# Control_board.net
KiCad netlist of a schematic drawn in EAGLE
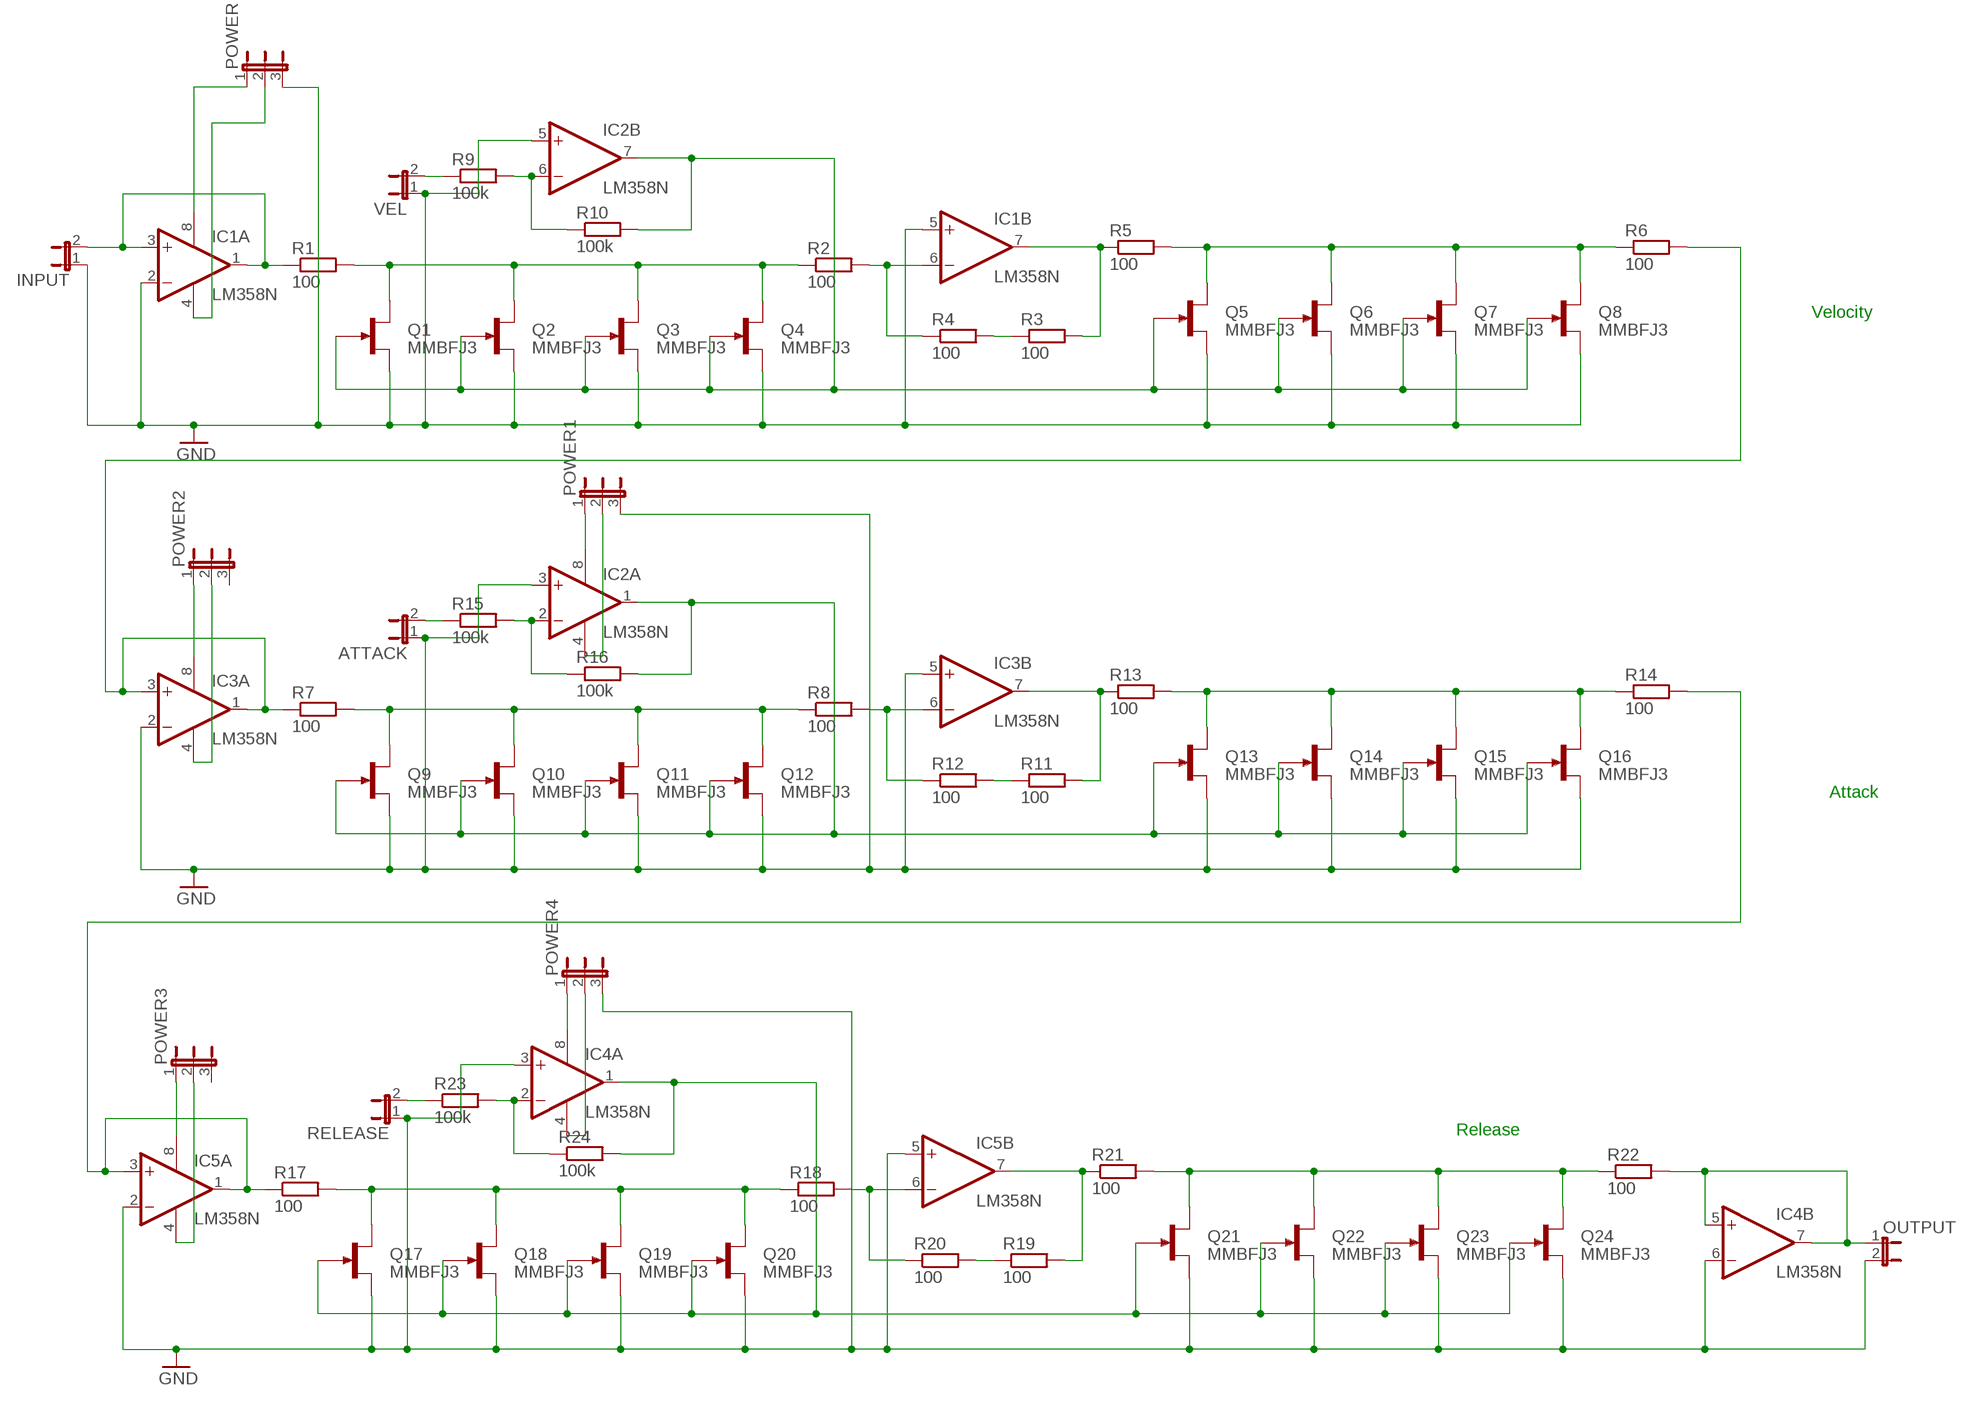
[diagram p0: schematic, sheet 1]

(export (version "E")
  (design (tool "Eeschema 10.0.6"))
  (components
    (comp (ref "ATTACK")
      (value "JP1E")
      (footprint "eagle-import:JP1")
      (libsource (lib "eagle-import") (part "JP1E"))
    )
    (comp (ref "IC1")
      (value "LM358N")
      (footprint "eagle-import:DIL08")
      (libsource (lib "eagle-import") (part "LM358N"))
    )
    (comp (ref "IC2")
      (value "LM358N")
      (footprint "eagle-import:DIL08")
      (libsource (lib "eagle-import") (part "LM358N"))
    )
    (comp (ref "IC3")
      (value "LM358N")
      (footprint "eagle-import:DIL08")
      (libsource (lib "eagle-import") (part "LM358N"))
    )
    (comp (ref "IC4")
      (value "LM358N")
      (footprint "eagle-import:DIL08")
      (libsource (lib "eagle-import") (part "LM358N"))
    )
    (comp (ref "IC5")
      (value "LM358N")
      (footprint "eagle-import:DIL08")
      (libsource (lib "eagle-import") (part "LM358N"))
    )
    (comp (ref "INPUT")
      (value "JP1E")
      (footprint "eagle-import:JP1")
      (libsource (lib "eagle-import") (part "JP1E"))
    )
    (comp (ref "OUTPUT")
      (value "JP1E")
      (footprint "eagle-import:JP1")
      (libsource (lib "eagle-import") (part "JP1E"))
    )
    (comp (ref "POWER")
      (value "JP2E")
      (footprint "eagle-import:JP2")
      (libsource (lib "eagle-import") (part "JP2E"))
    )
    (comp (ref "POWER1")
      (value "JP2E")
      (footprint "eagle-import:JP2")
      (libsource (lib "eagle-import") (part "JP2E"))
    )
    (comp (ref "POWER2")
      (value "JP2E")
      (footprint "eagle-import:JP2")
      (libsource (lib "eagle-import") (part "JP2E"))
    )
    (comp (ref "POWER3")
      (value "JP2E")
      (footprint "eagle-import:JP2")
      (libsource (lib "eagle-import") (part "JP2E"))
    )
    (comp (ref "POWER4")
      (value "JP2E")
      (footprint "eagle-import:JP2")
      (libsource (lib "eagle-import") (part "JP2E"))
    )
    (comp (ref "Q1")
      (value "MMBFJ3")
      (footprint "eagle-import:SOT23")
      (libsource (lib "eagle-import") (part "MMBFJ3"))
    )
    (comp (ref "Q2")
      (value "MMBFJ3")
      (footprint "eagle-import:SOT23")
      (libsource (lib "eagle-import") (part "MMBFJ3"))
    )
    (comp (ref "Q3")
      (value "MMBFJ3")
      (footprint "eagle-import:SOT23")
      (libsource (lib "eagle-import") (part "MMBFJ3"))
    )
    (comp (ref "Q4")
      (value "MMBFJ3")
      (footprint "eagle-import:SOT23")
      (libsource (lib "eagle-import") (part "MMBFJ3"))
    )
    (comp (ref "Q5")
      (value "MMBFJ3")
      (footprint "eagle-import:SOT23")
      (libsource (lib "eagle-import") (part "MMBFJ3"))
    )
    (comp (ref "Q6")
      (value "MMBFJ3")
      (footprint "eagle-import:SOT23")
      (libsource (lib "eagle-import") (part "MMBFJ3"))
    )
    (comp (ref "Q7")
      (value "MMBFJ3")
      (footprint "eagle-import:SOT23")
      (libsource (lib "eagle-import") (part "MMBFJ3"))
    )
    (comp (ref "Q8")
      (value "MMBFJ3")
      (footprint "eagle-import:SOT23")
      (libsource (lib "eagle-import") (part "MMBFJ3"))
    )
    (comp (ref "Q9")
      (value "MMBFJ3")
      (footprint "eagle-import:SOT23")
      (libsource (lib "eagle-import") (part "MMBFJ3"))
    )
    (comp (ref "Q10")
      (value "MMBFJ3")
      (footprint "eagle-import:SOT23")
      (libsource (lib "eagle-import") (part "MMBFJ3"))
    )
    (comp (ref "Q11")
      (value "MMBFJ3")
      (footprint "eagle-import:SOT23")
      (libsource (lib "eagle-import") (part "MMBFJ3"))
    )
    (comp (ref "Q12")
      (value "MMBFJ3")
      (footprint "eagle-import:SOT23")
      (libsource (lib "eagle-import") (part "MMBFJ3"))
    )
    (comp (ref "Q13")
      (value "MMBFJ3")
      (footprint "eagle-import:SOT23")
      (libsource (lib "eagle-import") (part "MMBFJ3"))
    )
    (comp (ref "Q14")
      (value "MMBFJ3")
      (footprint "eagle-import:SOT23")
      (libsource (lib "eagle-import") (part "MMBFJ3"))
    )
    (comp (ref "Q15")
      (value "MMBFJ3")
      (footprint "eagle-import:SOT23")
      (libsource (lib "eagle-import") (part "MMBFJ3"))
    )
    (comp (ref "Q16")
      (value "MMBFJ3")
      (footprint "eagle-import:SOT23")
      (libsource (lib "eagle-import") (part "MMBFJ3"))
    )
    (comp (ref "Q17")
      (value "MMBFJ3")
      (footprint "eagle-import:SOT23")
      (libsource (lib "eagle-import") (part "MMBFJ3"))
    )
    (comp (ref "Q18")
      (value "MMBFJ3")
      (footprint "eagle-import:SOT23")
      (libsource (lib "eagle-import") (part "MMBFJ3"))
    )
    (comp (ref "Q19")
      (value "MMBFJ3")
      (footprint "eagle-import:SOT23")
      (libsource (lib "eagle-import") (part "MMBFJ3"))
    )
    (comp (ref "Q20")
      (value "MMBFJ3")
      (footprint "eagle-import:SOT23")
      (libsource (lib "eagle-import") (part "MMBFJ3"))
    )
    (comp (ref "Q21")
      (value "MMBFJ3")
      (footprint "eagle-import:SOT23")
      (libsource (lib "eagle-import") (part "MMBFJ3"))
    )
    (comp (ref "Q22")
      (value "MMBFJ3")
      (footprint "eagle-import:SOT23")
      (libsource (lib "eagle-import") (part "MMBFJ3"))
    )
    (comp (ref "Q23")
      (value "MMBFJ3")
      (footprint "eagle-import:SOT23")
      (libsource (lib "eagle-import") (part "MMBFJ3"))
    )
    (comp (ref "Q24")
      (value "MMBFJ3")
      (footprint "eagle-import:SOT23")
      (libsource (lib "eagle-import") (part "MMBFJ3"))
    )
    (comp (ref "R1")
      (value "100")
      (footprint "eagle-import:0204_7")
      (libsource (lib "eagle-import") (part "R-EU_0204/7"))
    )
    (comp (ref "R2")
      (value "100")
      (footprint "eagle-import:0204_7")
      (libsource (lib "eagle-import") (part "R-EU_0204/7"))
    )
    (comp (ref "R3")
      (value "100")
      (footprint "eagle-import:0204_7")
      (libsource (lib "eagle-import") (part "R-EU_0204/7"))
    )
    (comp (ref "R4")
      (value "100")
      (footprint "eagle-import:0204_7")
      (libsource (lib "eagle-import") (part "R-EU_0204/7"))
    )
    (comp (ref "R5")
      (value "100")
      (footprint "eagle-import:0204_7")
      (libsource (lib "eagle-import") (part "R-EU_0204/7"))
    )
    (comp (ref "R6")
      (value "100")
      (footprint "eagle-import:0204_7")
      (libsource (lib "eagle-import") (part "R-EU_0204/7"))
    )
    (comp (ref "R7")
      (value "100")
      (footprint "eagle-import:0204_7")
      (libsource (lib "eagle-import") (part "R-EU_0204/7"))
    )
    (comp (ref "R8")
      (value "100")
      (footprint "eagle-import:0204_7")
      (libsource (lib "eagle-import") (part "R-EU_0204/7"))
    )
    (comp (ref "R9")
      (value "100k")
      (footprint "eagle-import:0204_7")
      (libsource (lib "eagle-import") (part "R-EU_0204/7"))
    )
    (comp (ref "R10")
      (value "100k")
      (footprint "eagle-import:0204_7")
      (libsource (lib "eagle-import") (part "R-EU_0204/7"))
    )
    (comp (ref "R11")
      (value "100")
      (footprint "eagle-import:0204_7")
      (libsource (lib "eagle-import") (part "R-EU_0204/7"))
    )
    (comp (ref "R12")
      (value "100")
      (footprint "eagle-import:0204_7")
      (libsource (lib "eagle-import") (part "R-EU_0204/7"))
    )
    (comp (ref "R13")
      (value "100")
      (footprint "eagle-import:0204_7")
      (libsource (lib "eagle-import") (part "R-EU_0204/7"))
    )
    (comp (ref "R14")
      (value "100")
      (footprint "eagle-import:0204_7")
      (libsource (lib "eagle-import") (part "R-EU_0204/7"))
    )
    (comp (ref "R15")
      (value "100k")
      (footprint "eagle-import:0204_7")
      (libsource (lib "eagle-import") (part "R-EU_0204/7"))
    )
    (comp (ref "R16")
      (value "100k")
      (footprint "eagle-import:0204_7")
      (libsource (lib "eagle-import") (part "R-EU_0204/7"))
    )
    (comp (ref "R17")
      (value "100")
      (footprint "eagle-import:0204_7")
      (libsource (lib "eagle-import") (part "R-EU_0204/7"))
    )
    (comp (ref "R18")
      (value "100")
      (footprint "eagle-import:0204_7")
      (libsource (lib "eagle-import") (part "R-EU_0204/7"))
    )
    (comp (ref "R19")
      (value "100")
      (footprint "eagle-import:0204_7")
      (libsource (lib "eagle-import") (part "R-EU_0204/7"))
    )
    (comp (ref "R20")
      (value "100")
      (footprint "eagle-import:0204_7")
      (libsource (lib "eagle-import") (part "R-EU_0204/7"))
    )
    (comp (ref "R21")
      (value "100")
      (footprint "eagle-import:0204_7")
      (libsource (lib "eagle-import") (part "R-EU_0204/7"))
    )
    (comp (ref "R22")
      (value "100")
      (footprint "eagle-import:0204_7")
      (libsource (lib "eagle-import") (part "R-EU_0204/7"))
    )
    (comp (ref "R23")
      (value "100k")
      (footprint "eagle-import:0204_7")
      (libsource (lib "eagle-import") (part "R-EU_0204/7"))
    )
    (comp (ref "R24")
      (value "100k")
      (footprint "eagle-import:0204_7")
      (libsource (lib "eagle-import") (part "R-EU_0204/7"))
    )
    (comp (ref "RELEASE")
      (value "JP1E")
      (footprint "eagle-import:JP1")
      (libsource (lib "eagle-import") (part "JP1E"))
    )
    (comp (ref "VEL")
      (value "JP1E")
      (footprint "eagle-import:JP1")
      (libsource (lib "eagle-import") (part "JP1E"))
    )
  )
  (nets
    (net (code "1") (name "GND") (class "Default")
      (node (ref "ATTACK") (pin "1") (pinfunction "1_1") (pintype "passive"))
      (node (ref "IC1") (pin "2") (pinfunction "-IN_2") (pintype "input"))
      (node (ref "IC1") (pin "5") (pinfunction "+IN_5") (pintype "input"))
      (node (ref "IC2") (pin "3") (pinfunction "+IN_3") (pintype "input"))
      (node (ref "IC2") (pin "5") (pinfunction "+IN_5") (pintype "input"))
      (node (ref "IC3") (pin "2") (pinfunction "-IN_2") (pintype "input"))
      (node (ref "IC3") (pin "5") (pinfunction "+IN_5") (pintype "input"))
      (node (ref "IC4") (pin "3") (pinfunction "+IN_3") (pintype "input"))
      (node (ref "IC4") (pin "6") (pinfunction "-IN_6") (pintype "input"))
      (node (ref "IC5") (pin "2") (pinfunction "-IN_2") (pintype "input"))
      (node (ref "IC5") (pin "5") (pinfunction "+IN_5") (pintype "input"))
      (node (ref "INPUT") (pin "1") (pinfunction "1_1") (pintype "passive"))
      (node (ref "OUTPUT") (pin "2") (pinfunction "2_2") (pintype "passive"))
      (node (ref "POWER") (pin "3") (pinfunction "3_3") (pintype "passive"))
      (node (ref "POWER1") (pin "3") (pinfunction "3_3") (pintype "passive"))
      (node (ref "POWER4") (pin "3") (pinfunction "3_3") (pintype "passive"))
      (node (ref "Q1") (pin "2") (pinfunction "S_2") (pintype "passive"))
      (node (ref "Q10") (pin "2") (pinfunction "S_2") (pintype "passive"))
      (node (ref "Q11") (pin "2") (pinfunction "S_2") (pintype "passive"))
      (node (ref "Q12") (pin "2") (pinfunction "S_2") (pintype "passive"))
      (node (ref "Q13") (pin "2") (pinfunction "S_2") (pintype "passive"))
      (node (ref "Q14") (pin "2") (pinfunction "S_2") (pintype "passive"))
      (node (ref "Q15") (pin "2") (pinfunction "S_2") (pintype "passive"))
      (node (ref "Q16") (pin "2") (pinfunction "S_2") (pintype "passive"))
      (node (ref "Q17") (pin "2") (pinfunction "S_2") (pintype "passive"))
      (node (ref "Q18") (pin "2") (pinfunction "S_2") (pintype "passive"))
      (node (ref "Q19") (pin "2") (pinfunction "S_2") (pintype "passive"))
      (node (ref "Q2") (pin "2") (pinfunction "S_2") (pintype "passive"))
      (node (ref "Q20") (pin "2") (pinfunction "S_2") (pintype "passive"))
      (node (ref "Q21") (pin "2") (pinfunction "S_2") (pintype "passive"))
      (node (ref "Q22") (pin "2") (pinfunction "S_2") (pintype "passive"))
      (node (ref "Q23") (pin "2") (pinfunction "S_2") (pintype "passive"))
      (node (ref "Q24") (pin "2") (pinfunction "S_2") (pintype "passive"))
      (node (ref "Q3") (pin "2") (pinfunction "S_2") (pintype "passive"))
      (node (ref "Q4") (pin "2") (pinfunction "S_2") (pintype "passive"))
      (node (ref "Q5") (pin "2") (pinfunction "S_2") (pintype "passive"))
      (node (ref "Q6") (pin "2") (pinfunction "S_2") (pintype "passive"))
      (node (ref "Q7") (pin "2") (pinfunction "S_2") (pintype "passive"))
      (node (ref "Q8") (pin "2") (pinfunction "S_2") (pintype "passive"))
      (node (ref "Q9") (pin "2") (pinfunction "S_2") (pintype "passive"))
      (node (ref "RELEASE") (pin "1") (pinfunction "1_1") (pintype "passive"))
      (node (ref "VEL") (pin "1") (pinfunction "1_1") (pintype "passive"))
    )
    (net (code "2") (name "Net-(ATTACK-Pad2)") (class "Default")
      (node (ref "ATTACK") (pin "2") (pinfunction "2_2") (pintype "passive"))
      (node (ref "R15") (pin "1") (pinfunction "1_1") (pintype "passive"))
    )
    (net (code "3") (name "Net-(IC1A-+IN)") (class "Default")
      (node (ref "IC1") (pin "1") (pinfunction "OUT_1") (pintype "output"))
      (node (ref "IC1") (pin "3") (pinfunction "+IN_3") (pintype "input"))
      (node (ref "INPUT") (pin "2") (pinfunction "2_2") (pintype "passive"))
      (node (ref "R1") (pin "1") (pinfunction "1_1") (pintype "passive"))
    )
    (net (code "4") (name "Net-(IC1B--IN)") (class "Default")
      (node (ref "IC1") (pin "6") (pinfunction "-IN_6") (pintype "input"))
      (node (ref "R2") (pin "2") (pinfunction "2_2") (pintype "passive"))
      (node (ref "R4") (pin "1") (pinfunction "1_1") (pintype "passive"))
    )
    (net (code "5") (name "Net-(IC1B-OUT)") (class "Default")
      (node (ref "IC1") (pin "7") (pinfunction "OUT_7") (pintype "output"))
      (node (ref "R3") (pin "2") (pinfunction "2_2") (pintype "passive"))
      (node (ref "R5") (pin "1") (pinfunction "1_1") (pintype "passive"))
    )
    (net (code "6") (name "Net-(IC1C-V+)") (class "Default")
      (node (ref "IC1") (pin "8") (pinfunction "V+_8") (pintype "power_in"))
      (node (ref "POWER") (pin "1") (pinfunction "1_1") (pintype "passive"))
    )
    (net (code "7") (name "Net-(IC1C-V-)") (class "Default")
      (node (ref "IC1") (pin "4") (pinfunction "V-_4") (pintype "power_in"))
      (node (ref "POWER") (pin "2") (pinfunction "2_2") (pintype "passive"))
    )
    (net (code "8") (name "Net-(IC2A--IN)") (class "Default")
      (node (ref "IC2") (pin "2") (pinfunction "-IN_2") (pintype "input"))
      (node (ref "R15") (pin "2") (pinfunction "2_2") (pintype "passive"))
      (node (ref "R16") (pin "1") (pinfunction "1_1") (pintype "passive"))
    )
    (net (code "9") (name "Net-(IC2A-OUT)") (class "Default")
      (node (ref "IC2") (pin "1") (pinfunction "OUT_1") (pintype "output"))
      (node (ref "Q10") (pin "3") (pinfunction "G_3") (pintype "passive"))
      (node (ref "Q11") (pin "3") (pinfunction "G_3") (pintype "passive"))
      (node (ref "Q12") (pin "3") (pinfunction "G_3") (pintype "passive"))
      (node (ref "Q13") (pin "3") (pinfunction "G_3") (pintype "passive"))
      (node (ref "Q14") (pin "3") (pinfunction "G_3") (pintype "passive"))
      (node (ref "Q15") (pin "3") (pinfunction "G_3") (pintype "passive"))
      (node (ref "Q16") (pin "3") (pinfunction "G_3") (pintype "passive"))
      (node (ref "Q9") (pin "3") (pinfunction "G_3") (pintype "passive"))
      (node (ref "R16") (pin "2") (pinfunction "2_2") (pintype "passive"))
    )
    (net (code "10") (name "Net-(IC2B--IN)") (class "Default")
      (node (ref "IC2") (pin "6") (pinfunction "-IN_6") (pintype "input"))
      (node (ref "R10") (pin "1") (pinfunction "1_1") (pintype "passive"))
      (node (ref "R9") (pin "2") (pinfunction "2_2") (pintype "passive"))
    )
    (net (code "11") (name "Net-(IC2B-OUT)") (class "Default")
      (node (ref "IC2") (pin "7") (pinfunction "OUT_7") (pintype "output"))
      (node (ref "Q1") (pin "3") (pinfunction "G_3") (pintype "passive"))
      (node (ref "Q2") (pin "3") (pinfunction "G_3") (pintype "passive"))
      (node (ref "Q3") (pin "3") (pinfunction "G_3") (pintype "passive"))
      (node (ref "Q4") (pin "3") (pinfunction "G_3") (pintype "passive"))
      (node (ref "Q5") (pin "3") (pinfunction "G_3") (pintype "passive"))
      (node (ref "Q6") (pin "3") (pinfunction "G_3") (pintype "passive"))
      (node (ref "Q7") (pin "3") (pinfunction "G_3") (pintype "passive"))
      (node (ref "Q8") (pin "3") (pinfunction "G_3") (pintype "passive"))
      (node (ref "R10") (pin "2") (pinfunction "2_2") (pintype "passive"))
    )
    (net (code "12") (name "Net-(IC2C-V+)") (class "Default")
      (node (ref "IC2") (pin "8") (pinfunction "V+_8") (pintype "power_in"))
      (node (ref "POWER1") (pin "1") (pinfunction "1_1") (pintype "passive"))
    )
    (net (code "13") (name "Net-(IC2C-V-)") (class "Default")
      (node (ref "IC2") (pin "4") (pinfunction "V-_4") (pintype "power_in"))
      (node (ref "POWER1") (pin "2") (pinfunction "2_2") (pintype "passive"))
    )
    (net (code "14") (name "Net-(IC3A-+IN)") (class "Default")
      (node (ref "IC3") (pin "1") (pinfunction "OUT_1") (pintype "output"))
      (node (ref "IC3") (pin "3") (pinfunction "+IN_3") (pintype "input"))
      (node (ref "R6") (pin "2") (pinfunction "2_2") (pintype "passive"))
      (node (ref "R7") (pin "1") (pinfunction "1_1") (pintype "passive"))
    )
    (net (code "15") (name "Net-(IC3B--IN)") (class "Default")
      (node (ref "IC3") (pin "6") (pinfunction "-IN_6") (pintype "input"))
      (node (ref "R12") (pin "1") (pinfunction "1_1") (pintype "passive"))
      (node (ref "R8") (pin "2") (pinfunction "2_2") (pintype "passive"))
    )
    (net (code "16") (name "Net-(IC3B-OUT)") (class "Default")
      (node (ref "IC3") (pin "7") (pinfunction "OUT_7") (pintype "output"))
      (node (ref "R11") (pin "2") (pinfunction "2_2") (pintype "passive"))
      (node (ref "R13") (pin "1") (pinfunction "1_1") (pintype "passive"))
    )
    (net (code "17") (name "Net-(IC3C-V+)") (class "Default")
      (node (ref "IC3") (pin "8") (pinfunction "V+_8") (pintype "power_in"))
      (node (ref "POWER2") (pin "1") (pinfunction "1_1") (pintype "passive"))
    )
    (net (code "18") (name "Net-(IC3C-V-)") (class "Default")
      (node (ref "IC3") (pin "4") (pinfunction "V-_4") (pintype "power_in"))
      (node (ref "POWER2") (pin "2") (pinfunction "2_2") (pintype "passive"))
    )
    (net (code "19") (name "Net-(IC4A--IN)") (class "Default")
      (node (ref "IC4") (pin "2") (pinfunction "-IN_2") (pintype "input"))
      (node (ref "R23") (pin "2") (pinfunction "2_2") (pintype "passive"))
      (node (ref "R24") (pin "1") (pinfunction "1_1") (pintype "passive"))
    )
    (net (code "20") (name "Net-(IC4A-OUT)") (class "Default")
      (node (ref "IC4") (pin "1") (pinfunction "OUT_1") (pintype "output"))
      (node (ref "Q17") (pin "3") (pinfunction "G_3") (pintype "passive"))
      (node (ref "Q18") (pin "3") (pinfunction "G_3") (pintype "passive"))
      (node (ref "Q19") (pin "3") (pinfunction "G_3") (pintype "passive"))
      (node (ref "Q20") (pin "3") (pinfunction "G_3") (pintype "passive"))
      (node (ref "Q21") (pin "3") (pinfunction "G_3") (pintype "passive"))
      (node (ref "Q22") (pin "3") (pinfunction "G_3") (pintype "passive"))
      (node (ref "Q23") (pin "3") (pinfunction "G_3") (pintype "passive"))
      (node (ref "Q24") (pin "3") (pinfunction "G_3") (pintype "passive"))
      (node (ref "R24") (pin "2") (pinfunction "2_2") (pintype "passive"))
    )
    (net (code "21") (name "Net-(IC4B-+IN)") (class "Default")
      (node (ref "IC4") (pin "5") (pinfunction "+IN_5") (pintype "input"))
      (node (ref "IC4") (pin "7") (pinfunction "OUT_7") (pintype "output"))
      (node (ref "OUTPUT") (pin "1") (pinfunction "1_1") (pintype "passive"))
      (node (ref "R22") (pin "2") (pinfunction "2_2") (pintype "passive"))
    )
    (net (code "22") (name "Net-(IC4C-V+)") (class "Default")
      (node (ref "IC4") (pin "8") (pinfunction "V+_8") (pintype "power_in"))
      (node (ref "POWER4") (pin "1") (pinfunction "1_1") (pintype "passive"))
    )
    (net (code "23") (name "Net-(IC4C-V-)") (class "Default")
      (node (ref "IC4") (pin "4") (pinfunction "V-_4") (pintype "power_in"))
      (node (ref "POWER4") (pin "2") (pinfunction "2_2") (pintype "passive"))
    )
    (net (code "24") (name "Net-(IC5A-+IN)") (class "Default")
      (node (ref "IC5") (pin "1") (pinfunction "OUT_1") (pintype "output"))
      (node (ref "IC5") (pin "3") (pinfunction "+IN_3") (pintype "input"))
      (node (ref "R14") (pin "2") (pinfunction "2_2") (pintype "passive"))
      (node (ref "R17") (pin "1") (pinfunction "1_1") (pintype "passive"))
    )
    (net (code "25") (name "Net-(IC5B--IN)") (class "Default")
      (node (ref "IC5") (pin "6") (pinfunction "-IN_6") (pintype "input"))
      (node (ref "R18") (pin "2") (pinfunction "2_2") (pintype "passive"))
      (node (ref "R20") (pin "1") (pinfunction "1_1") (pintype "passive"))
    )
    (net (code "26") (name "Net-(IC5B-OUT)") (class "Default")
      (node (ref "IC5") (pin "7") (pinfunction "OUT_7") (pintype "output"))
      (node (ref "R19") (pin "2") (pinfunction "2_2") (pintype "passive"))
      (node (ref "R21") (pin "1") (pinfunction "1_1") (pintype "passive"))
    )
    (net (code "27") (name "Net-(IC5C-V+)") (class "Default")
      (node (ref "IC5") (pin "8") (pinfunction "V+_8") (pintype "power_in"))
      (node (ref "POWER3") (pin "1") (pinfunction "1_1") (pintype "passive"))
    )
    (net (code "28") (name "Net-(IC5C-V-)") (class "Default")
      (node (ref "IC5") (pin "4") (pinfunction "V-_4") (pintype "power_in"))
      (node (ref "POWER3") (pin "2") (pinfunction "2_2") (pintype "passive"))
    )
    (net (code "29") (name "Net-(Q1-D)") (class "Default")
      (node (ref "Q1") (pin "1") (pinfunction "D_1") (pintype "passive"))
      (node (ref "Q2") (pin "1") (pinfunction "D_1") (pintype "passive"))
      (node (ref "Q3") (pin "1") (pinfunction "D_1") (pintype "passive"))
      (node (ref "Q4") (pin "1") (pinfunction "D_1") (pintype "passive"))
      (node (ref "R1") (pin "2") (pinfunction "2_2") (pintype "passive"))
      (node (ref "R2") (pin "1") (pinfunction "1_1") (pintype "passive"))
    )
    (net (code "30") (name "Net-(Q5-D)") (class "Default")
      (node (ref "Q5") (pin "1") (pinfunction "D_1") (pintype "passive"))
      (node (ref "Q6") (pin "1") (pinfunction "D_1") (pintype "passive"))
      (node (ref "Q7") (pin "1") (pinfunction "D_1") (pintype "passive"))
      (node (ref "Q8") (pin "1") (pinfunction "D_1") (pintype "passive"))
      (node (ref "R5") (pin "2") (pinfunction "2_2") (pintype "passive"))
      (node (ref "R6") (pin "1") (pinfunction "1_1") (pintype "passive"))
    )
    (net (code "31") (name "Net-(Q10-D)") (class "Default")
      (node (ref "Q10") (pin "1") (pinfunction "D_1") (pintype "passive"))
      (node (ref "Q11") (pin "1") (pinfunction "D_1") (pintype "passive"))
      (node (ref "Q12") (pin "1") (pinfunction "D_1") (pintype "passive"))
      (node (ref "Q9") (pin "1") (pinfunction "D_1") (pintype "passive"))
      (node (ref "R7") (pin "2") (pinfunction "2_2") (pintype "passive"))
      (node (ref "R8") (pin "1") (pinfunction "1_1") (pintype "passive"))
    )
    (net (code "32") (name "Net-(Q13-D)") (class "Default")
      (node (ref "Q13") (pin "1") (pinfunction "D_1") (pintype "passive"))
      (node (ref "Q14") (pin "1") (pinfunction "D_1") (pintype "passive"))
      (node (ref "Q15") (pin "1") (pinfunction "D_1") (pintype "passive"))
      (node (ref "Q16") (pin "1") (pinfunction "D_1") (pintype "passive"))
      (node (ref "R13") (pin "2") (pinfunction "2_2") (pintype "passive"))
      (node (ref "R14") (pin "1") (pinfunction "1_1") (pintype "passive"))
    )
    (net (code "33") (name "Net-(Q17-D)") (class "Default")
      (node (ref "Q17") (pin "1") (pinfunction "D_1") (pintype "passive"))
      (node (ref "Q18") (pin "1") (pinfunction "D_1") (pintype "passive"))
      (node (ref "Q19") (pin "1") (pinfunction "D_1") (pintype "passive"))
      (node (ref "Q20") (pin "1") (pinfunction "D_1") (pintype "passive"))
      (node (ref "R17") (pin "2") (pinfunction "2_2") (pintype "passive"))
      (node (ref "R18") (pin "1") (pinfunction "1_1") (pintype "passive"))
    )
    (net (code "34") (name "Net-(Q21-D)") (class "Default")
      (node (ref "Q21") (pin "1") (pinfunction "D_1") (pintype "passive"))
      (node (ref "Q22") (pin "1") (pinfunction "D_1") (pintype "passive"))
      (node (ref "Q23") (pin "1") (pinfunction "D_1") (pintype "passive"))
      (node (ref "Q24") (pin "1") (pinfunction "D_1") (pintype "passive"))
      (node (ref "R21") (pin "2") (pinfunction "2_2") (pintype "passive"))
      (node (ref "R22") (pin "1") (pinfunction "1_1") (pintype "passive"))
    )
    (net (code "35") (name "Net-(R3-Pad1)") (class "Default")
      (node (ref "R3") (pin "1") (pinfunction "1_1") (pintype "passive"))
      (node (ref "R4") (pin "2") (pinfunction "2_2") (pintype "passive"))
    )
    (net (code "36") (name "Net-(R9-Pad1)") (class "Default")
      (node (ref "R9") (pin "1") (pinfunction "1_1") (pintype "passive"))
      (node (ref "VEL") (pin "2") (pinfunction "2_2") (pintype "passive"))
    )
    (net (code "37") (name "Net-(R11-Pad1)") (class "Default")
      (node (ref "R11") (pin "1") (pinfunction "1_1") (pintype "passive"))
      (node (ref "R12") (pin "2") (pinfunction "2_2") (pintype "passive"))
    )
    (net (code "38") (name "Net-(R19-Pad1)") (class "Default")
      (node (ref "R19") (pin "1") (pinfunction "1_1") (pintype "passive"))
      (node (ref "R20") (pin "2") (pinfunction "2_2") (pintype "passive"))
    )
    (net (code "39") (name "Net-(R23-Pad1)") (class "Default")
      (node (ref "R23") (pin "1") (pinfunction "1_1") (pintype "passive"))
      (node (ref "RELEASE") (pin "2") (pinfunction "2_2") (pintype "passive"))
    )
    (net (code "40") (name "unconnected-(POWER2-Pad3)") (class "Default")
      (node (ref "POWER2") (pin "3") (pinfunction "3_3") (pintype "passive"))
    )
    (net (code "41") (name "unconnected-(POWER3-Pad3)") (class "Default")
      (node (ref "POWER3") (pin "3") (pinfunction "3_3") (pintype "passive"))
    )
  )
)
